# design.net
KiCad netlist of a schematic drawn in Altium Designer
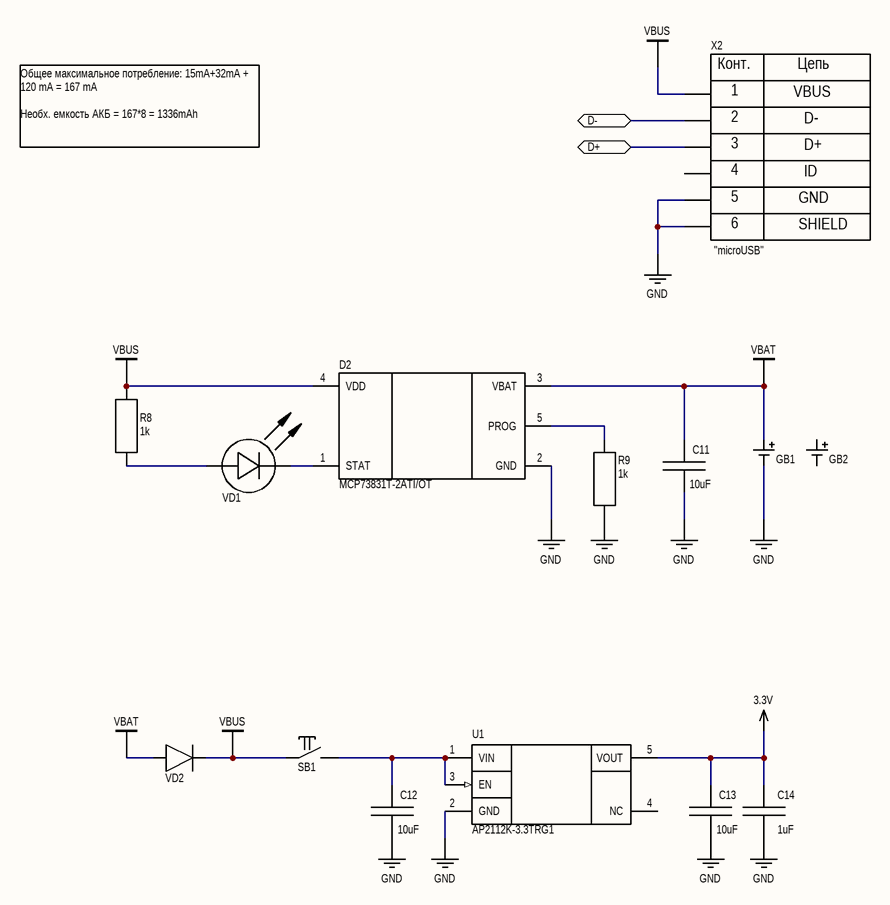
[diagram p0: Схема питания.SchDoc]

(export (version "E")
  (design (tool "Eeschema 10.0.6"))
  (components
    (comp (ref "C11")
      (value "10uF")
      (footprint "standard_dis:CH1206C")
      (description "CAP CER 10UF 16V X7R 1206")
      (fields (field (name "MANUFACTURER") "Murata Electronics"))
      (libsource (lib "Discrete") (part "Capacitor"))
    )
    (comp (ref "C12")
      (value "10uF")
      (footprint "standard_dis:CH1206C")
      (description "CAP CER 10UF 16V X7R 1206")
      (fields (field (name "MANUFACTURER") "Murata Electronics"))
      (libsource (lib "Discrete") (part "Capacitor"))
    )
    (comp (ref "C13")
      (value "10uF")
      (footprint "standard_dis:CH1206C")
      (description "CAP CER 10UF 16V X7R 1206")
      (fields (field (name "MANUFACTURER") "Murata Electronics"))
      (libsource (lib "Discrete") (part "Capacitor"))
    )
    (comp (ref "C14")
      (value "1uF")
      (footprint "standard_dis:CH0603C")
      (fields (field (name "MANUFACTURER") "Samsung Electro-Mechanics"))
      (libsource (lib "Discrete") (part "Capacitor"))
    )
    (comp (ref "D2")
      (value "MCP73831T-2ATI/OT")
      (footprint "standard_ps:SOT23-5")
      (description "Li-ion chargers")
      (fields (field (name "MANUFACTURER") "Microchip Technology"))
      (libsource (lib "Power Supplies") (part "MCP73831T-2ATI/OT"))
    )
    (comp (ref "GB1")
      (value "1-12 шт., перезаряжаемые литий-полимерные аккумуляторы 3,7 в, 1260100 мАч")
      (footprint "BAT: 34.5X52MM (only pads)")
      (fields (field (name "MANUFACTURER") "AliExpress"))
      (libsource (lib "Power Supplies") (part "Battery_1CELL"))
    )
    (comp (ref "GB2")
      (value "LP103450JH+PCM+PTC+2 WIRES 70MM")
      (footprint "custom_ps:BAT: 34.5X52MM")
      (description "LiPo Battery")
      (fields (field (name "MANUFACTURER") "Jauch Quartz"))
      (libsource (lib "Power Supplies") (part "LP103450JH+PCM+PTC+2 WIRES 70MM"))
    )
    (comp (ref "R8")
      (value "1k")
      (footprint "standard_dis:CH0603R")
      (fields (field (name "MANUFACTURER") "YAGEO"))
      (libsource (lib "Discrete") (part "Resistor"))
    )
    (comp (ref "R9")
      (value "1k")
      (footprint "standard_dis:CH0603R")
      (fields (field (name "MANUFACTURER") "YAGEO"))
      (libsource (lib "Discrete") (part "Resistor"))
    )
    (comp (ref "SB1")
      (value "\"Кнопка\"")
      (footprint "BUT: 2PADS 2x2mm")
      (description "Tactile switches")
      (fields (field (name "MANUFACTURER") "CW Industries"))
      (libsource (lib "Connectors") (part "Tactile switches"))
    )
    (comp (ref "U1")
      (value "AP2112K-3.3TRG1")
      (footprint "standard_ps:SOT-25")
      (description "IC REG LINEAR 3.3V 600MA SOT25")
      (fields (field (name "MANUFACTURER") "Diodes Incorporated"))
      (libsource (lib "Power Supplies") (part "AP2112K-3.3TRG1"))
    )
    (comp (ref "VD1")
      (value "*")
      (footprint "standard_dis:CH0603LR")
      (fields (field (name "MANUFACTURER") "Lite-On Inc."))
      (libsource (lib "Discrete") (part "LED"))
    )
    (comp (ref "VD2")
      (value "BAT54XV2T1G")
      (footprint "standard_d:SOD523")
      (fields (field (name "MANUFACTURER") "onsemi"))
      (libsource (lib "Diods") (part "Diod"))
    )
    (comp (ref "X2")
      (value "\"microUSB\"")
      (footprint "custom_con:CON: MicroUSB - TH")
      (description "USB")
      (fields (field (name "MANUFACTURER") "Molex"))
      (libsource (lib "Connectors") (part "USB - micro AB"))
    )
  )
  (nets
    (net (code "1") (name "/D+") (class "Default")
      (node (ref "X2") (pin "3") (pinfunction "3_3") (pintype "passive"))
    )
    (net (code "2") (name "/D-") (class "Default")
      (node (ref "X2") (pin "2") (pinfunction "2_2") (pintype "passive"))
    )
    (net (code "3") (name "3.3V") (class "Default")
      (node (ref "C13") (pin "1") (pinfunction "1_1") (pintype "passive"))
      (node (ref "C14") (pin "1") (pinfunction "1_1") (pintype "passive"))
      (node (ref "U1") (pin "5") (pinfunction "VOUT_5") (pintype "power_in"))
    )
    (net (code "4") (name "GND") (class "Default")
      (node (ref "C11") (pin "2") (pinfunction "2_2") (pintype "passive"))
      (node (ref "C12") (pin "2") (pinfunction "2_2") (pintype "passive"))
      (node (ref "C13") (pin "2") (pinfunction "2_2") (pintype "passive"))
      (node (ref "C14") (pin "2") (pinfunction "2_2") (pintype "passive"))
      (node (ref "D2") (pin "2") (pinfunction "GND_2") (pintype "passive"))
      (node (ref "GB1") (pin "2") (pinfunction "-_2") (pintype "passive"))
      (node (ref "R9") (pin "1") (pinfunction "1_1") (pintype "passive"))
      (node (ref "U1") (pin "2") (pinfunction "GND_2") (pintype "power_in"))
      (node (ref "X2") (pin "5") (pinfunction "5_5") (pintype "passive"))
      (node (ref "X2") (pin "6") (pinfunction "6_6") (pintype "passive"))
    )
    (net (code "5") (name "Net-(D2-PROG)") (class "Default")
      (node (ref "D2") (pin "5") (pinfunction "PROG_5") (pintype "passive"))
      (node (ref "R9") (pin "2") (pinfunction "2_2") (pintype "passive"))
    )
    (net (code "6") (name "Net-(D2-STAT)") (class "Default")
      (node (ref "D2") (pin "1") (pinfunction "STAT_1") (pintype "open_collector"))
      (node (ref "VD1") (pin "2") (pinfunction "C_2") (pintype "passive"))
    )
    (net (code "7") (name "Net-(U1-EN)") (class "Default")
      (node (ref "C12") (pin "1") (pinfunction "1_1") (pintype "passive"))
      (node (ref "SB1") (pin "2") (pinfunction "2_2") (pintype "passive"))
      (node (ref "U1") (pin "1") (pinfunction "VIN_1") (pintype "power_in"))
      (node (ref "U1") (pin "3") (pinfunction "EN_3") (pintype "input"))
    )
    (net (code "8") (name "Net-(VD1-A)") (class "Default")
      (node (ref "R8") (pin "1") (pinfunction "1_1") (pintype "passive"))
      (node (ref "VD1") (pin "1") (pinfunction "A_1") (pintype "passive"))
    )
    (net (code "9") (name "VBAT") (class "Default")
      (node (ref "C11") (pin "1") (pinfunction "1_1") (pintype "passive"))
      (node (ref "D2") (pin "3") (pinfunction "VBAT_3") (pintype "passive"))
      (node (ref "GB1") (pin "1") (pinfunction "+_1") (pintype "passive"))
      (node (ref "VD2") (pin "1") (pinfunction "1_1") (pintype "passive"))
    )
    (net (code "10") (name "VBUS") (class "Default")
      (node (ref "D2") (pin "4") (pinfunction "VDD_4") (pintype "passive"))
      (node (ref "R8") (pin "2") (pinfunction "2_2") (pintype "passive"))
      (node (ref "SB1") (pin "1") (pinfunction "1_1") (pintype "passive"))
      (node (ref "VD2") (pin "2") (pinfunction "2_2") (pintype "passive"))
      (node (ref "X2") (pin "1") (pintype "passive"))
    )
    (net (code "11") (name "unconnected-(GB2-+-Pad1)") (class "Default")
      (node (ref "GB2") (pin "1") (pinfunction "+_1") (pintype "passive"))
    )
    (net (code "12") (name "unconnected-(GB2---Pad2)") (class "Default")
      (node (ref "GB2") (pin "2") (pinfunction "-_2") (pintype "passive"))
    )
    (net (code "13") (name "unconnected-(U1-NC-Pad4)") (class "Default")
      (node (ref "U1") (pin "4") (pinfunction "NC_4") (pintype "passive"))
    )
    (net (code "14") (name "unconnected-(X2-Pad4)") (class "Default")
      (node (ref "X2") (pin "4") (pinfunction "4_4") (pintype "passive"))
    )
  )
)
